# CapSense.net
KiCad netlist of a schematic drawn in Altium Designer
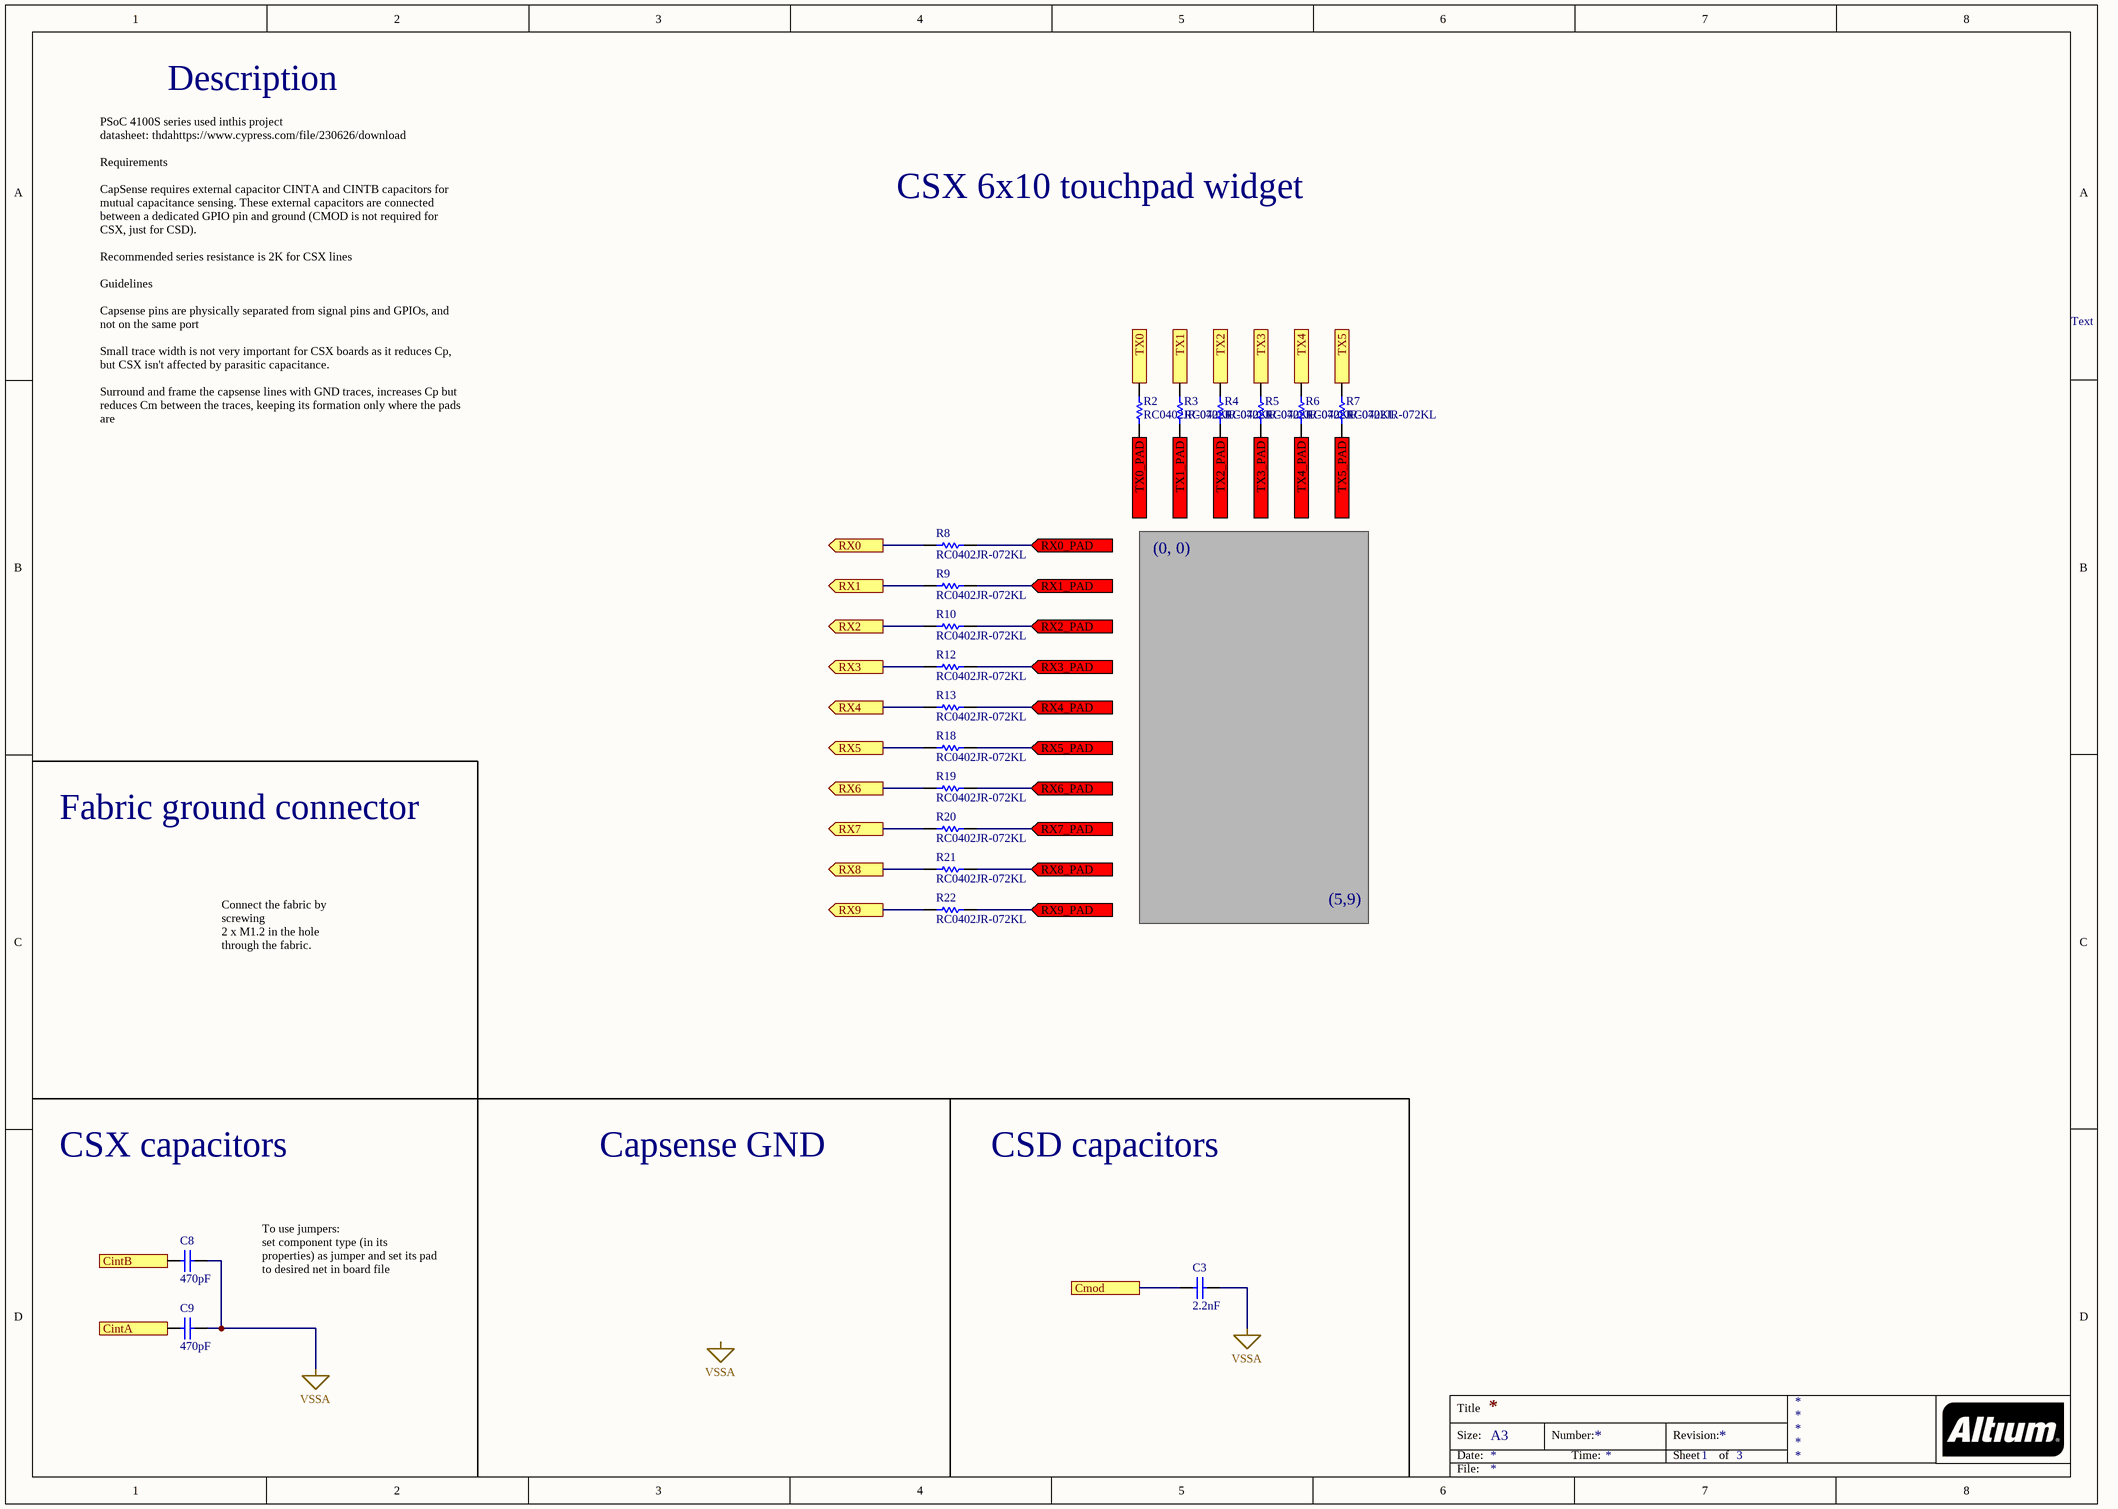
[diagram p0: CapSense.SchDoc]

(export (version "E")
  (design (tool "Eeschema 10.0.6"))
  (components
    (comp (ref "C3")
      (value "2.2nF")
      (footprint "CAPC1005X56X25ML10T15")
      (fields
        (field (name "MANUFACTURER") "AVX Interconnect / Elco")
        (field (name "PART NUMBER") "04026D105KAT2A")
      )
      (libsource (lib "Altium Content Vault") (part "CAP"))
    )
    (comp (ref "C8")
      (value "470pF")
      (footprint "CAPC0603(1608)100_N")
      (description "CAP 470pF 10V ±10% 0603 (1608 Metric) Thickness 1mm SMD")
      (fields (field (name "TOLERANCE") "Â±10%"))
      (libsource (lib "Altium Content Vault") (part "CAP"))
    )
    (comp (ref "C9")
      (value "470pF")
      (footprint "CAPC0603(1608)100_N")
      (description "CAP 470pF 10V ±10% 0603 (1608 Metric) Thickness 1mm SMD")
      (fields (field (name "TOLERANCE") "Â±10%"))
      (libsource (lib "Altium Content Vault") (part "CAP"))
    )
    (comp (ref "R2")
      (value "RC0402JR-072KL")
      (footprint "RESC1005X40X25ML05T10")
      (fields (field (name "MANUFACTURER") "Yageo / Phycomp"))
      (libsource (lib "Altium Content Vault") (part "RES"))
    )
    (comp (ref "R3")
      (value "RC0402JR-072KL")
      (footprint "RESC1005X40X25ML05T10")
      (fields (field (name "MANUFACTURER") "Yageo / Phycomp"))
      (libsource (lib "Altium Content Vault") (part "RES"))
    )
    (comp (ref "R4")
      (value "RC0402JR-072KL")
      (footprint "RESC1005X40X25ML05T10")
      (fields (field (name "MANUFACTURER") "Yageo / Phycomp"))
      (libsource (lib "Altium Content Vault") (part "RES"))
    )
    (comp (ref "R5")
      (value "RC0402JR-072KL")
      (footprint "RESC1005X40X25ML05T10")
      (fields (field (name "MANUFACTURER") "Yageo / Phycomp"))
      (libsource (lib "Altium Content Vault") (part "RES"))
    )
    (comp (ref "R6")
      (value "RC0402JR-072KL")
      (footprint "RESC1005X40X25ML05T10")
      (fields (field (name "MANUFACTURER") "Yageo / Phycomp"))
      (libsource (lib "Altium Content Vault") (part "RES"))
    )
    (comp (ref "R7")
      (value "RC0402JR-072KL")
      (footprint "RESC1005X40X25ML05T10")
      (fields (field (name "MANUFACTURER") "Yageo / Phycomp"))
      (libsource (lib "Altium Content Vault") (part "RES"))
    )
    (comp (ref "R8")
      (value "RC0402JR-072KL")
      (footprint "RESC1005X40X25ML05T10")
      (fields (field (name "MANUFACTURER") "Yageo / Phycomp"))
      (libsource (lib "Altium Content Vault") (part "RES"))
    )
    (comp (ref "R9")
      (value "RC0402JR-072KL")
      (footprint "RESC1005X40X25ML05T10")
      (fields (field (name "MANUFACTURER") "Yageo / Phycomp"))
      (libsource (lib "Altium Content Vault") (part "RES"))
    )
    (comp (ref "R10")
      (value "RC0402JR-072KL")
      (footprint "RESC1005X40X25ML05T10")
      (fields (field (name "MANUFACTURER") "Yageo / Phycomp"))
      (libsource (lib "Altium Content Vault") (part "RES"))
    )
    (comp (ref "R12")
      (value "RC0402JR-072KL")
      (footprint "RESC1005X40X25ML05T10")
      (fields (field (name "MANUFACTURER") "Yageo / Phycomp"))
      (libsource (lib "Altium Content Vault") (part "RES"))
    )
    (comp (ref "R13")
      (value "RC0402JR-072KL")
      (footprint "RESC1005X40X25ML05T10")
      (fields (field (name "MANUFACTURER") "Yageo / Phycomp"))
      (libsource (lib "Altium Content Vault") (part "RES"))
    )
    (comp (ref "R18")
      (value "RC0402JR-072KL")
      (footprint "RESC1005X40X25ML05T10")
      (fields (field (name "MANUFACTURER") "Yageo / Phycomp"))
      (libsource (lib "Altium Content Vault") (part "RES"))
    )
    (comp (ref "R19")
      (value "RC0402JR-072KL")
      (footprint "RESC1005X40X25ML05T10")
      (fields (field (name "MANUFACTURER") "Yageo / Phycomp"))
      (libsource (lib "Altium Content Vault") (part "RES"))
    )
    (comp (ref "R20")
      (value "RC0402JR-072KL")
      (footprint "RESC1005X40X25ML05T10")
      (fields (field (name "MANUFACTURER") "Yageo / Phycomp"))
      (libsource (lib "Altium Content Vault") (part "RES"))
    )
    (comp (ref "R21")
      (value "RC0402JR-072KL")
      (footprint "RESC1005X40X25ML05T10")
      (fields (field (name "MANUFACTURER") "Yageo / Phycomp"))
      (libsource (lib "Altium Content Vault") (part "RES"))
    )
    (comp (ref "R22")
      (value "RC0402JR-072KL")
      (footprint "RESC1005X40X25ML05T10")
      (fields (field (name "MANUFACTURER") "Yageo / Phycomp"))
      (libsource (lib "Altium Content Vault") (part "RES"))
    )
  )
  (nets
    (net (code "1") (name "/CintA") (class "Default")
      (node (ref "C9") (pin "1") (pinfunction "1_1") (pintype "passive"))
    )
    (net (code "2") (name "/CintB") (class "Default")
      (node (ref "C8") (pin "1") (pinfunction "1_1") (pintype "passive"))
    )
    (net (code "3") (name "/Cmod") (class "Default")
      (node (ref "C3") (pin "1") (pinfunction "1_1") (pintype "passive"))
    )
    (net (code "4") (name "/RX0") (class "Default")
      (node (ref "R8") (pin "1") (pinfunction "1_1") (pintype "passive"))
    )
    (net (code "5") (name "/RX0_PAD") (class "Default")
      (node (ref "R8") (pin "2") (pinfunction "2_2") (pintype "passive"))
    )
    (net (code "6") (name "/RX1") (class "Default")
      (node (ref "R9") (pin "1") (pinfunction "1_1") (pintype "passive"))
    )
    (net (code "7") (name "/RX1_PAD") (class "Default")
      (node (ref "R9") (pin "2") (pinfunction "2_2") (pintype "passive"))
    )
    (net (code "8") (name "/RX2") (class "Default")
      (node (ref "R10") (pin "1") (pinfunction "1_1") (pintype "passive"))
    )
    (net (code "9") (name "/RX2_PAD") (class "Default")
      (node (ref "R10") (pin "2") (pinfunction "2_2") (pintype "passive"))
    )
    (net (code "10") (name "/RX3") (class "Default")
      (node (ref "R12") (pin "1") (pinfunction "1_1") (pintype "passive"))
    )
    (net (code "11") (name "/RX3_PAD") (class "Default")
      (node (ref "R12") (pin "2") (pinfunction "2_2") (pintype "passive"))
    )
    (net (code "12") (name "/RX4") (class "Default")
      (node (ref "R13") (pin "1") (pinfunction "1_1") (pintype "passive"))
    )
    (net (code "13") (name "/RX4_PAD") (class "Default")
      (node (ref "R13") (pin "2") (pinfunction "2_2") (pintype "passive"))
    )
    (net (code "14") (name "/RX5") (class "Default")
      (node (ref "R18") (pin "1") (pinfunction "1_1") (pintype "passive"))
    )
    (net (code "15") (name "/RX5_PAD") (class "Default")
      (node (ref "R18") (pin "2") (pinfunction "2_2") (pintype "passive"))
    )
    (net (code "16") (name "/RX6") (class "Default")
      (node (ref "R19") (pin "1") (pinfunction "1_1") (pintype "passive"))
    )
    (net (code "17") (name "/RX6_PAD") (class "Default")
      (node (ref "R19") (pin "2") (pinfunction "2_2") (pintype "passive"))
    )
    (net (code "18") (name "/RX7") (class "Default")
      (node (ref "R20") (pin "1") (pinfunction "1_1") (pintype "passive"))
    )
    (net (code "19") (name "/RX7_PAD") (class "Default")
      (node (ref "R20") (pin "2") (pinfunction "2_2") (pintype "passive"))
    )
    (net (code "20") (name "/RX8") (class "Default")
      (node (ref "R21") (pin "1") (pinfunction "1_1") (pintype "passive"))
    )
    (net (code "21") (name "/RX8_PAD") (class "Default")
      (node (ref "R21") (pin "2") (pinfunction "2_2") (pintype "passive"))
    )
    (net (code "22") (name "/RX9") (class "Default")
      (node (ref "R22") (pin "1") (pinfunction "1_1") (pintype "passive"))
    )
    (net (code "23") (name "/RX9_PAD") (class "Default")
      (node (ref "R22") (pin "2") (pinfunction "2_2") (pintype "passive"))
    )
    (net (code "24") (name "/TX0") (class "Default")
      (node (ref "R2") (pin "2") (pinfunction "2_2") (pintype "passive"))
    )
    (net (code "25") (name "/TX0_PAD") (class "Default")
      (node (ref "R2") (pin "1") (pinfunction "1_1") (pintype "passive"))
    )
    (net (code "26") (name "/TX1") (class "Default")
      (node (ref "R3") (pin "2") (pinfunction "2_2") (pintype "passive"))
    )
    (net (code "27") (name "/TX1_PAD") (class "Default")
      (node (ref "R3") (pin "1") (pinfunction "1_1") (pintype "passive"))
    )
    (net (code "28") (name "/TX2") (class "Default")
      (node (ref "R4") (pin "2") (pinfunction "2_2") (pintype "passive"))
    )
    (net (code "29") (name "/TX2_PAD") (class "Default")
      (node (ref "R4") (pin "1") (pinfunction "1_1") (pintype "passive"))
    )
    (net (code "30") (name "/TX3") (class "Default")
      (node (ref "R5") (pin "2") (pinfunction "2_2") (pintype "passive"))
    )
    (net (code "31") (name "/TX3_PAD") (class "Default")
      (node (ref "R5") (pin "1") (pinfunction "1_1") (pintype "passive"))
    )
    (net (code "32") (name "/TX4") (class "Default")
      (node (ref "R6") (pin "2") (pinfunction "2_2") (pintype "passive"))
    )
    (net (code "33") (name "/TX4_PAD") (class "Default")
      (node (ref "R6") (pin "1") (pinfunction "1_1") (pintype "passive"))
    )
    (net (code "34") (name "/TX5") (class "Default")
      (node (ref "R7") (pin "2") (pinfunction "2_2") (pintype "passive"))
    )
    (net (code "35") (name "/TX5_PAD") (class "Default")
      (node (ref "R7") (pin "1") (pinfunction "1_1") (pintype "passive"))
    )
    (net (code "36") (name "VSSA") (class "Default")
      (node (ref "C3") (pin "2") (pinfunction "2_2") (pintype "passive"))
      (node (ref "C8") (pin "2") (pinfunction "2_2") (pintype "passive"))
      (node (ref "C9") (pin "2") (pinfunction "2_2") (pintype "passive"))
    )
  )
)
